# mainProbe_ESP12_mill.net
KiCad netlist of a schematic drawn in EAGLE
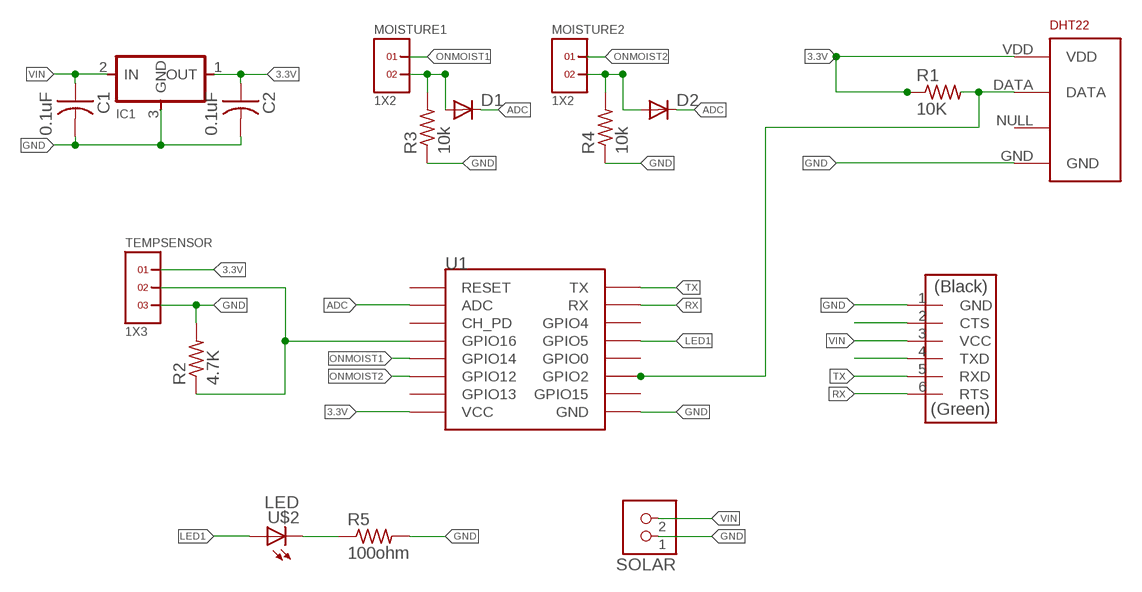
[diagram p0: schematic, sheet 1]

(export (version "E")
  (design (tool "Eeschema 10.0.6"))
  (components
    (comp (ref "C1")
      (value "0.1uF")
      (footprint "eagle-import:C1206")
      (libsource (lib "eagle-import") (part "CAP-US1206"))
    )
    (comp (ref "C2")
      (value "0.1uF")
      (footprint "eagle-import:C1206")
      (libsource (lib "eagle-import") (part "CAP-US1206"))
    )
    (comp (ref "D1")
      (value "DIODESOD123")
      (footprint "eagle-import:SOD123")
      (libsource (lib "eagle-import") (part "DIODESOD123"))
    )
    (comp (ref "D2")
      (value "DIODESOD123")
      (footprint "eagle-import:SOD123")
      (libsource (lib "eagle-import") (part "DIODESOD123"))
    )
    (comp (ref "DHT22")
      (value "RHT03_DHT-22_AM2302")
      (footprint "eagle-import:RHT03_DHT-22")
      (libsource (lib "eagle-import") (part "RHT03_DHT-22_AM2302"))
    )
    (comp (ref "IC1")
      (value "REGULATORSOT23")
      (footprint "eagle-import:SOT23")
      (libsource (lib "eagle-import") (part "REGULATORSOT23"))
    )
    (comp (ref "MOISTURE1")
      (value "1X2")
      (footprint "eagle-import:1X2")
      (libsource (lib "eagle-import") (part "1X2"))
    )
    (comp (ref "MOISTURE2")
      (value "1X2")
      (footprint "eagle-import:1X2")
      (libsource (lib "eagle-import") (part "1X2"))
    )
    (comp (ref "R1")
      (value "10K")
      (footprint "eagle-import:R1206")
      (libsource (lib "eagle-import") (part "RES-US1206"))
    )
    (comp (ref "R2")
      (value "4.7K")
      (footprint "eagle-import:R1206")
      (libsource (lib "eagle-import") (part "RES-US1206"))
    )
    (comp (ref "R3")
      (value "10k")
      (footprint "eagle-import:R1206")
      (libsource (lib "eagle-import") (part "RES-US1206"))
    )
    (comp (ref "R4")
      (value "10k")
      (footprint "eagle-import:R1206")
      (libsource (lib "eagle-import") (part "RES-US1206"))
    )
    (comp (ref "R5")
      (value "100ohm")
      (footprint "eagle-import:R1206")
      (libsource (lib "eagle-import") (part "RES-US1206"))
    )
    (comp (ref "SOLAR")
      (value "TERM-1X02-ADAFRUIT")
      (footprint "eagle-import:3.5MMTERM")
      (libsource (lib "eagle-import") (part "TERM-1X02-ADAFRUIT"))
    )
    (comp (ref "TEMPSENSOR")
      (value "1X3")
      (footprint "eagle-import:1X3")
      (libsource (lib "eagle-import") (part "1X3"))
    )
    (comp (ref "U$1")
      (value "FTDI-SMD-HEADER")
      (footprint "eagle-import:1X06SMD")
      (libsource (lib "eagle-import") (part "FTDI-SMD-HEADER"))
    )
    (comp (ref "U$2")
      (value "LED")
      (footprint "eagle-import:LED1206")
      (libsource (lib "eagle-import") (part "LED"))
    )
    (comp (ref "U1")
      (value "ESP12")
      (footprint "eagle-import:ESP12")
      (libsource (lib "eagle-import") (part "ESP12"))
    )
  )
  (nets
    (net (code "1") (name "3.3V") (class "Default")
      (node (ref "C2") (pin "1") (pinfunction "1_1") (pintype "passive"))
      (node (ref "DHT22") (pin "VDD") (pinfunction "VDD_VDD") (pintype "power_in"))
      (node (ref "IC1") (pin "1") (pinfunction "OUT_1") (pintype "bidirectional"))
      (node (ref "R1") (pin "1") (pinfunction "1_1") (pintype "passive"))
      (node (ref "TEMPSENSOR") (pin "1") (pinfunction "1_1") (pintype "bidirectional"))
      (node (ref "U1") (pin "VCC") (pinfunction "VCC_VCC") (pintype "bidirectional"))
    )
    (net (code "2") (name "ADC") (class "Default")
      (node (ref "D1") (pin "CATHODE") (pinfunction "C_CATHODE") (pintype "passive"))
      (node (ref "D2") (pin "CATHODE") (pinfunction "C_CATHODE") (pintype "passive"))
      (node (ref "U1") (pin "ADC") (pinfunction "ADC_ADC") (pintype "bidirectional"))
    )
    (net (code "3") (name "GND") (class "Default")
      (node (ref "C1") (pin "2") (pinfunction "2_2") (pintype "passive"))
      (node (ref "C2") (pin "2") (pinfunction "2_2") (pintype "passive"))
      (node (ref "DHT22") (pin "GND") (pinfunction "GND_GND") (pintype "power_in"))
      (node (ref "IC1") (pin "3") (pinfunction "GND_3") (pintype "bidirectional"))
      (node (ref "R2") (pin "2") (pinfunction "2_2") (pintype "passive"))
      (node (ref "R3") (pin "1") (pinfunction "1_1") (pintype "passive"))
      (node (ref "R4") (pin "1") (pinfunction "1_1") (pintype "passive"))
      (node (ref "R5") (pin "2") (pinfunction "2_2") (pintype "passive"))
      (node (ref "SOLAR") (pin "1") (pinfunction "1_1") (pintype "passive"))
      (node (ref "TEMPSENSOR") (pin "3") (pinfunction "3_3") (pintype "bidirectional"))
      (node (ref "U$1") (pin "1") (pinfunction "GND_1") (pintype "bidirectional"))
      (node (ref "U1") (pin "GND") (pinfunction "GND_GND") (pintype "bidirectional"))
    )
    (net (code "4") (name "LED1") (class "Default")
      (node (ref "U$2") (pin "1") (pinfunction "A_1") (pintype "passive"))
      (node (ref "U1") (pin "GPIO5") (pinfunction "GPIO5_GPIO5") (pintype "bidirectional"))
    )
    (net (code "5") (name "Net-(D1-A)") (class "Default")
      (node (ref "D1") (pin "ANODE") (pinfunction "A_ANODE") (pintype "passive"))
      (node (ref "MOISTURE1") (pin "2") (pinfunction "2_2") (pintype "bidirectional"))
      (node (ref "R3") (pin "2") (pinfunction "2_2") (pintype "passive"))
    )
    (net (code "6") (name "Net-(D2-A)") (class "Default")
      (node (ref "D2") (pin "ANODE") (pinfunction "A_ANODE") (pintype "passive"))
      (node (ref "MOISTURE2") (pin "2") (pinfunction "2_2") (pintype "bidirectional"))
      (node (ref "R4") (pin "2") (pinfunction "2_2") (pintype "passive"))
    )
    (net (code "7") (name "Net-(DHT22-PadDATA)") (class "Default")
      (node (ref "DHT22") (pin "DATA") (pinfunction "DATA_DATA") (pintype "bidirectional"))
      (node (ref "R1") (pin "2") (pinfunction "2_2") (pintype "passive"))
      (node (ref "U1") (pin "GPIO2") (pinfunction "GPIO2_GPIO2") (pintype "bidirectional"))
    )
    (net (code "8") (name "Net-(R2-Pad1)") (class "Default")
      (node (ref "R2") (pin "1") (pinfunction "1_1") (pintype "passive"))
      (node (ref "TEMPSENSOR") (pin "2") (pinfunction "2_2") (pintype "bidirectional"))
      (node (ref "U1") (pin "GPIO16") (pinfunction "GPIO16_GPIO16") (pintype "bidirectional"))
    )
    (net (code "9") (name "Net-(U$2-C)") (class "Default")
      (node (ref "R5") (pin "1") (pinfunction "1_1") (pintype "passive"))
      (node (ref "U$2") (pin "2") (pinfunction "C_2") (pintype "passive"))
    )
    (net (code "10") (name "ONMOIST1") (class "Default")
      (node (ref "MOISTURE1") (pin "1") (pinfunction "1_1") (pintype "bidirectional"))
      (node (ref "U1") (pin "GPIO14") (pinfunction "GPIO14_GPIO14") (pintype "bidirectional"))
    )
    (net (code "11") (name "ONMOIST2") (class "Default")
      (node (ref "MOISTURE2") (pin "1") (pinfunction "1_1") (pintype "bidirectional"))
      (node (ref "U1") (pin "GPIO12") (pinfunction "GPIO12_GPIO12") (pintype "bidirectional"))
    )
    (net (code "12") (name "RX") (class "Default")
      (node (ref "U$1") (pin "6") (pinfunction "RTS_6") (pintype "bidirectional"))
      (node (ref "U1") (pin "RX") (pinfunction "RX_RX") (pintype "bidirectional"))
    )
    (net (code "13") (name "TX") (class "Default")
      (node (ref "U$1") (pin "5") (pinfunction "RXD_5") (pintype "bidirectional"))
      (node (ref "U1") (pin "TX") (pinfunction "TX_TX") (pintype "bidirectional"))
    )
    (net (code "14") (name "VIN") (class "Default")
      (node (ref "C1") (pin "1") (pinfunction "1_1") (pintype "passive"))
      (node (ref "IC1") (pin "2") (pinfunction "IN_2") (pintype "bidirectional"))
      (node (ref "SOLAR") (pin "2") (pinfunction "2_2") (pintype "passive"))
      (node (ref "U$1") (pin "3") (pinfunction "VCC_3") (pintype "bidirectional"))
    )
    (net (code "15") (name "unconnected-(DHT22-PadNULL)") (class "Default")
      (node (ref "DHT22") (pin "NULL") (pinfunction "NULL_NULL") (pintype "no_connect"))
    )
    (net (code "16") (name "unconnected-(U$1-CTS-Pad2)") (class "Default")
      (node (ref "U$1") (pin "2") (pinfunction "CTS_2") (pintype "bidirectional"))
    )
    (net (code "17") (name "unconnected-(U$1-TXD-Pad4)") (class "Default")
      (node (ref "U$1") (pin "4") (pinfunction "TXD_4") (pintype "bidirectional"))
    )
    (net (code "18") (name "unconnected-(U1-PadCH_PD)") (class "Default")
      (node (ref "U1") (pin "CH_PD") (pinfunction "CH_PD_CH_PD") (pintype "bidirectional"))
    )
    (net (code "19") (name "unconnected-(U1-PadGPIO0)") (class "Default")
      (node (ref "U1") (pin "GPIO0") (pinfunction "GPIO0_GPIO0") (pintype "bidirectional"))
    )
    (net (code "20") (name "unconnected-(U1-PadGPIO4)") (class "Default")
      (node (ref "U1") (pin "GPIO4") (pinfunction "GPIO4_GPIO4") (pintype "bidirectional"))
    )
    (net (code "21") (name "unconnected-(U1-PadGPIO13)") (class "Default")
      (node (ref "U1") (pin "GPIO13") (pinfunction "GPIO13_GPIO13") (pintype "bidirectional"))
    )
    (net (code "22") (name "unconnected-(U1-PadGPIO15)") (class "Default")
      (node (ref "U1") (pin "GPIO15") (pinfunction "GPIO15_GPIO15") (pintype "bidirectional"))
    )
    (net (code "23") (name "unconnected-(U1-PadRESET)") (class "Default")
      (node (ref "U1") (pin "RESET") (pinfunction "RESET_RESET") (pintype "bidirectional"))
    )
  )
)
